# TapClip_v3.net
KiCad netlist of a schematic drawn in EAGLE
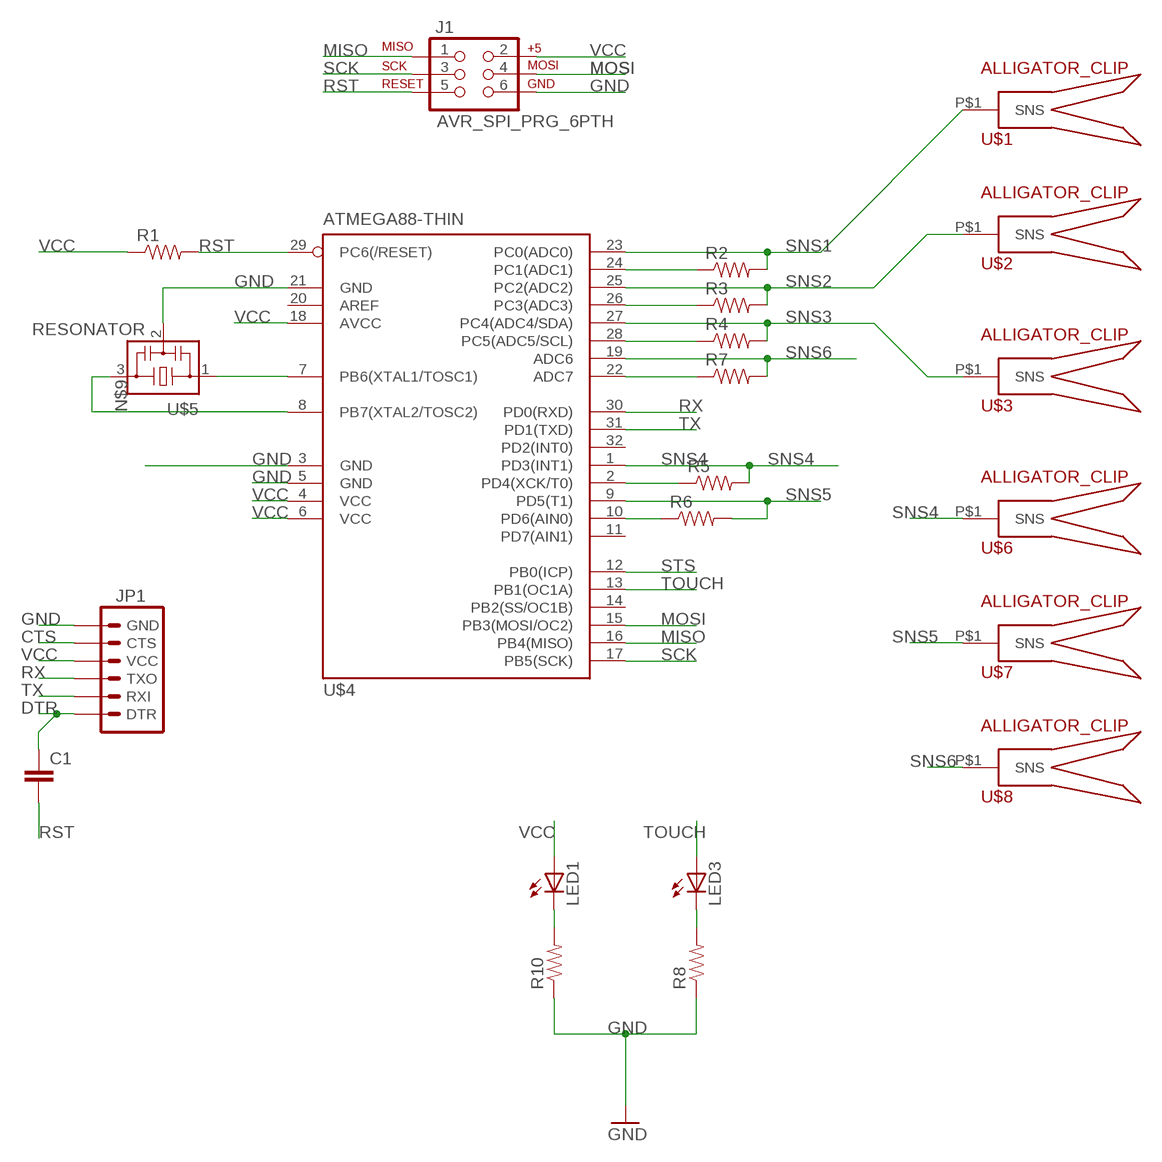
[diagram p0: schematic, sheet 1]

(export (version "E")
  (design (tool "Eeschema 10.0.6"))
  (components
    (comp (ref "C1")
      (value "CAP0603-CAP")
      (footprint "eagle-import:0603-CAP")
      (libsource (lib "eagle-import") (part "CAP0603-CAP"))
    )
    (comp (ref "J1")
      (value "AVR_SPI_PRG_6PTH")
      (footprint "eagle-import:2X3")
      (libsource (lib "eagle-import") (part "AVR_SPI_PRG_6PTH"))
    )
    (comp (ref "JP1")
      (value "ARDUINO_SERIAL_PROGRAMSMD")
      (footprint "eagle-import:1X06-SMD")
      (libsource (lib "eagle-import") (part "ARDUINO_SERIAL_PROGRAMSMD"))
    )
    (comp (ref "LED1")
      (value "LED1206")
      (footprint "eagle-import:LED-1206")
      (libsource (lib "eagle-import") (part "LED1206"))
    )
    (comp (ref "LED3")
      (value "LED1206")
      (footprint "eagle-import:LED-1206")
      (libsource (lib "eagle-import") (part "LED1206"))
    )
    (comp (ref "R1")
      (value "RESISTOR0603-RES")
      (footprint "eagle-import:0603-RES")
      (libsource (lib "eagle-import") (part "RESISTOR0603-RES"))
    )
    (comp (ref "R2")
      (value "RESISTOR0603-RES")
      (footprint "eagle-import:0603-RES")
      (libsource (lib "eagle-import") (part "RESISTOR0603-RES"))
    )
    (comp (ref "R3")
      (value "RESISTOR0603-RES")
      (footprint "eagle-import:0603-RES")
      (libsource (lib "eagle-import") (part "RESISTOR0603-RES"))
    )
    (comp (ref "R4")
      (value "RESISTOR0603-RES")
      (footprint "eagle-import:0603-RES")
      (libsource (lib "eagle-import") (part "RESISTOR0603-RES"))
    )
    (comp (ref "R5")
      (value "RESISTOR0603-RES")
      (footprint "eagle-import:0603-RES")
      (libsource (lib "eagle-import") (part "RESISTOR0603-RES"))
    )
    (comp (ref "R6")
      (value "RESISTOR0603-RES")
      (footprint "eagle-import:0603-RES")
      (libsource (lib "eagle-import") (part "RESISTOR0603-RES"))
    )
    (comp (ref "R7")
      (value "RESISTOR0603-RES")
      (footprint "eagle-import:0603-RES")
      (libsource (lib "eagle-import") (part "RESISTOR0603-RES"))
    )
    (comp (ref "R8")
      (value "RESISTOR1206")
      (footprint "eagle-import:1206")
      (libsource (lib "eagle-import") (part "RESISTOR1206"))
    )
    (comp (ref "R10")
      (value "RESISTOR1206")
      (footprint "eagle-import:1206")
      (libsource (lib "eagle-import") (part "RESISTOR1206"))
    )
    (comp (ref "U$1")
      (value "ALLIGATOR_CLIP")
      (footprint "eagle-import:ALLIGATOR_CLIP")
      (libsource (lib "eagle-import") (part "ALLIGATOR_CLIP"))
    )
    (comp (ref "U$2")
      (value "ALLIGATOR_CLIP")
      (footprint "eagle-import:ALLIGATOR_CLIP")
      (libsource (lib "eagle-import") (part "ALLIGATOR_CLIP"))
    )
    (comp (ref "U$3")
      (value "ALLIGATOR_CLIP")
      (footprint "eagle-import:ALLIGATOR_CLIP")
      (libsource (lib "eagle-import") (part "ALLIGATOR_CLIP"))
    )
    (comp (ref "U$4")
      (value "ATMEGA88-THIN")
      (footprint "eagle-import:TQFP32-08THIN")
      (libsource (lib "eagle-import") (part "ATMEGA88-THIN"))
    )
    (comp (ref "U$5")
      (value "RESONATOR")
      (footprint "eagle-import:EFOBM")
      (libsource (lib "eagle-import") (part "RESONATOR"))
    )
    (comp (ref "U$6")
      (value "ALLIGATOR_CLIP")
      (footprint "eagle-import:ALLIGATOR_CLIP")
      (libsource (lib "eagle-import") (part "ALLIGATOR_CLIP"))
    )
    (comp (ref "U$7")
      (value "ALLIGATOR_CLIP")
      (footprint "eagle-import:ALLIGATOR_CLIP")
      (libsource (lib "eagle-import") (part "ALLIGATOR_CLIP"))
    )
    (comp (ref "U$8")
      (value "ALLIGATOR_CLIP")
      (footprint "eagle-import:ALLIGATOR_CLIP")
      (libsource (lib "eagle-import") (part "ALLIGATOR_CLIP"))
    )
  )
  (nets
    (net (code "1") (name "/CTS") (class "Default")
      (node (ref "JP1") (pin "5") (pinfunction "CTS_5") (pintype "passive"))
    )
    (net (code "2") (name "/DTR") (class "Default")
      (node (ref "C1") (pin "1") (pinfunction "1_1") (pintype "passive"))
      (node (ref "JP1") (pin "1") (pinfunction "DTR_1") (pintype "passive"))
    )
    (net (code "3") (name "/MISO") (class "Default")
      (node (ref "J1") (pin "1") (pinfunction "1_1") (pintype "passive"))
      (node (ref "U$4") (pin "16") (pinfunction "PB4(MISO)_16") (pintype "bidirectional"))
    )
    (net (code "4") (name "/MOSI") (class "Default")
      (node (ref "J1") (pin "4") (pinfunction "4_4") (pintype "passive"))
      (node (ref "U$4") (pin "15") (pinfunction "PB3(MOSI/OC2)_15") (pintype "bidirectional"))
    )
    (net (code "5") (name "/N$9") (class "Default")
      (node (ref "U$4") (pin "8") (pinfunction "PB7(XTAL2/TOSC2)_8") (pintype "bidirectional"))
      (node (ref "U$5") (pin "3") (pinfunction "3_3") (pintype "passive"))
    )
    (net (code "6") (name "/RST") (class "Default")
      (node (ref "C1") (pin "2") (pinfunction "2_2") (pintype "passive"))
      (node (ref "J1") (pin "5") (pinfunction "5_5") (pintype "passive"))
      (node (ref "R1") (pin "2") (pinfunction "2_2") (pintype "passive"))
      (node (ref "U$4") (pin "29") (pinfunction "PC6(/RESET)_29") (pintype "bidirectional"))
    )
    (net (code "7") (name "/RX") (class "Default")
      (node (ref "JP1") (pin "3") (pinfunction "TXO_3") (pintype "passive"))
      (node (ref "U$4") (pin "30") (pinfunction "PD0(RXD)_30") (pintype "bidirectional"))
    )
    (net (code "8") (name "/SCK") (class "Default")
      (node (ref "J1") (pin "3") (pinfunction "3_3") (pintype "passive"))
      (node (ref "U$4") (pin "17") (pinfunction "PB5(SCK)_17") (pintype "bidirectional"))
    )
    (net (code "9") (name "/SNS1") (class "Default")
      (node (ref "R2") (pin "2") (pinfunction "2_2") (pintype "passive"))
      (node (ref "U$1") (pin "P$1") (pinfunction "SNS_P$1") (pintype "bidirectional"))
      (node (ref "U$4") (pin "23") (pinfunction "PC0(ADC0)_23") (pintype "bidirectional"))
    )
    (net (code "10") (name "/SNS2") (class "Default")
      (node (ref "R3") (pin "2") (pinfunction "2_2") (pintype "passive"))
      (node (ref "U$2") (pin "P$1") (pinfunction "SNS_P$1") (pintype "bidirectional"))
      (node (ref "U$4") (pin "25") (pinfunction "PC2(ADC2)_25") (pintype "bidirectional"))
    )
    (net (code "11") (name "/SNS3") (class "Default")
      (node (ref "R4") (pin "2") (pinfunction "2_2") (pintype "passive"))
      (node (ref "U$3") (pin "P$1") (pinfunction "SNS_P$1") (pintype "bidirectional"))
      (node (ref "U$4") (pin "27") (pinfunction "PC4(ADC4/SDA)_27") (pintype "bidirectional"))
    )
    (net (code "12") (name "/SNS4") (class "Default")
      (node (ref "R5") (pin "2") (pinfunction "2_2") (pintype "passive"))
      (node (ref "U$4") (pin "1") (pinfunction "PD3(INT1)_1") (pintype "bidirectional"))
      (node (ref "U$6") (pin "P$1") (pinfunction "SNS_P$1") (pintype "bidirectional"))
    )
    (net (code "13") (name "/SNS5") (class "Default")
      (node (ref "R6") (pin "2") (pinfunction "2_2") (pintype "passive"))
      (node (ref "U$4") (pin "9") (pinfunction "PD5(T1)_9") (pintype "bidirectional"))
      (node (ref "U$7") (pin "P$1") (pinfunction "SNS_P$1") (pintype "bidirectional"))
    )
    (net (code "14") (name "/SNS6") (class "Default")
      (node (ref "R7") (pin "2") (pinfunction "2_2") (pintype "passive"))
      (node (ref "U$4") (pin "19") (pinfunction "ADC6_19") (pintype "bidirectional"))
      (node (ref "U$8") (pin "P$1") (pinfunction "SNS_P$1") (pintype "bidirectional"))
    )
    (net (code "15") (name "/STS") (class "Default")
      (node (ref "U$4") (pin "12") (pinfunction "PB0(ICP)_12") (pintype "bidirectional"))
    )
    (net (code "16") (name "/TOUCH") (class "Default")
      (node (ref "LED3") (pin "A") (pinfunction "A_A") (pintype "passive"))
      (node (ref "U$4") (pin "13") (pinfunction "PB1(OC1A)_13") (pintype "bidirectional"))
    )
    (net (code "17") (name "/TX") (class "Default")
      (node (ref "JP1") (pin "2") (pinfunction "RXI_2") (pintype "passive"))
      (node (ref "U$4") (pin "31") (pinfunction "PD1(TXD)_31") (pintype "bidirectional"))
    )
    (net (code "18") (name "/VCC") (class "Default")
      (node (ref "J1") (pin "2") (pinfunction "2_2") (pintype "passive"))
      (node (ref "JP1") (pin "4") (pinfunction "VCC_4") (pintype "passive"))
      (node (ref "LED1") (pin "A") (pinfunction "A_A") (pintype "passive"))
      (node (ref "R1") (pin "1") (pinfunction "1_1") (pintype "passive"))
      (node (ref "U$4") (pin "18") (pinfunction "AVCC_18") (pintype "power_in"))
      (node (ref "U$4") (pin "4") (pinfunction "VCC_4") (pintype "power_in"))
      (node (ref "U$4") (pin "6") (pinfunction "VCC_6") (pintype "power_in"))
    )
    (net (code "19") (name "GND") (class "Default")
      (node (ref "J1") (pin "6") (pinfunction "6_6") (pintype "passive"))
      (node (ref "JP1") (pin "6") (pinfunction "GND_6") (pintype "passive"))
      (node (ref "R10") (pin "1") (pinfunction "1_1") (pintype "passive"))
      (node (ref "R8") (pin "1") (pinfunction "1_1") (pintype "passive"))
      (node (ref "U$4") (pin "21") (pinfunction "GND_21") (pintype "power_in"))
      (node (ref "U$4") (pin "3") (pinfunction "GND_3") (pintype "power_in"))
      (node (ref "U$4") (pin "5") (pinfunction "GND_5") (pintype "power_in"))
      (node (ref "U$5") (pin "2") (pinfunction "2_2") (pintype "passive"))
    )
    (net (code "20") (name "Net-(LED1-PadC)") (class "Default")
      (node (ref "LED1") (pin "C") (pinfunction "C_C") (pintype "passive"))
      (node (ref "R10") (pin "2") (pinfunction "2_2") (pintype "passive"))
    )
    (net (code "21") (name "Net-(LED3-PadC)") (class "Default")
      (node (ref "LED3") (pin "C") (pinfunction "C_C") (pintype "passive"))
      (node (ref "R8") (pin "2") (pinfunction "2_2") (pintype "passive"))
    )
    (net (code "22") (name "Net-(U$4-ADC7)") (class "Default")
      (node (ref "R7") (pin "1") (pinfunction "1_1") (pintype "passive"))
      (node (ref "U$4") (pin "22") (pinfunction "ADC7_22") (pintype "bidirectional"))
    )
    (net (code "23") (name "Net-(U$4-PB6(XTAL1{slash}TOSC1))") (class "Default")
      (node (ref "U$4") (pin "7") (pinfunction "PB6(XTAL1/TOSC1)_7") (pintype "bidirectional"))
      (node (ref "U$5") (pin "1") (pinfunction "1_1") (pintype "passive"))
    )
    (net (code "24") (name "Net-(U$4-PC1(ADC1))") (class "Default")
      (node (ref "R2") (pin "1") (pinfunction "1_1") (pintype "passive"))
      (node (ref "U$4") (pin "24") (pinfunction "PC1(ADC1)_24") (pintype "bidirectional"))
    )
    (net (code "25") (name "Net-(U$4-PC3(ADC3))") (class "Default")
      (node (ref "R3") (pin "1") (pinfunction "1_1") (pintype "passive"))
      (node (ref "U$4") (pin "26") (pinfunction "PC3(ADC3)_26") (pintype "bidirectional"))
    )
    (net (code "26") (name "Net-(U$4-PC5(ADC5{slash}SCL))") (class "Default")
      (node (ref "R4") (pin "1") (pinfunction "1_1") (pintype "passive"))
      (node (ref "U$4") (pin "28") (pinfunction "PC5(ADC5/SCL)_28") (pintype "bidirectional"))
    )
    (net (code "27") (name "Net-(U$4-PD4(XCK{slash}T0))") (class "Default")
      (node (ref "R5") (pin "1") (pinfunction "1_1") (pintype "passive"))
      (node (ref "U$4") (pin "2") (pinfunction "PD4(XCK/T0)_2") (pintype "bidirectional"))
    )
    (net (code "28") (name "Net-(U$4-PD6(AIN0))") (class "Default")
      (node (ref "R6") (pin "1") (pinfunction "1_1") (pintype "passive"))
      (node (ref "U$4") (pin "10") (pinfunction "PD6(AIN0)_10") (pintype "bidirectional"))
    )
    (net (code "29") (name "unconnected-(U$4-AREF-Pad20)") (class "Default")
      (node (ref "U$4") (pin "20") (pinfunction "AREF_20") (pintype "passive"))
    )
    (net (code "30") (name "unconnected-(U$4-PB2(SS{slash}OC1B)-Pad14)") (class "Default")
      (node (ref "U$4") (pin "14") (pinfunction "PB2(SS/OC1B)_14") (pintype "bidirectional"))
    )
    (net (code "31") (name "unconnected-(U$4-PD2(INT0)-Pad32)") (class "Default")
      (node (ref "U$4") (pin "32") (pinfunction "PD2(INT0)_32") (pintype "bidirectional"))
    )
    (net (code "32") (name "unconnected-(U$4-PD7(AIN1)-Pad11)") (class "Default")
      (node (ref "U$4") (pin "11") (pinfunction "PD7(AIN1)_11") (pintype "bidirectional"))
    )
  )
)
